# audio_spectrum.net
KiCad netlist of a schematic drawn in EAGLE
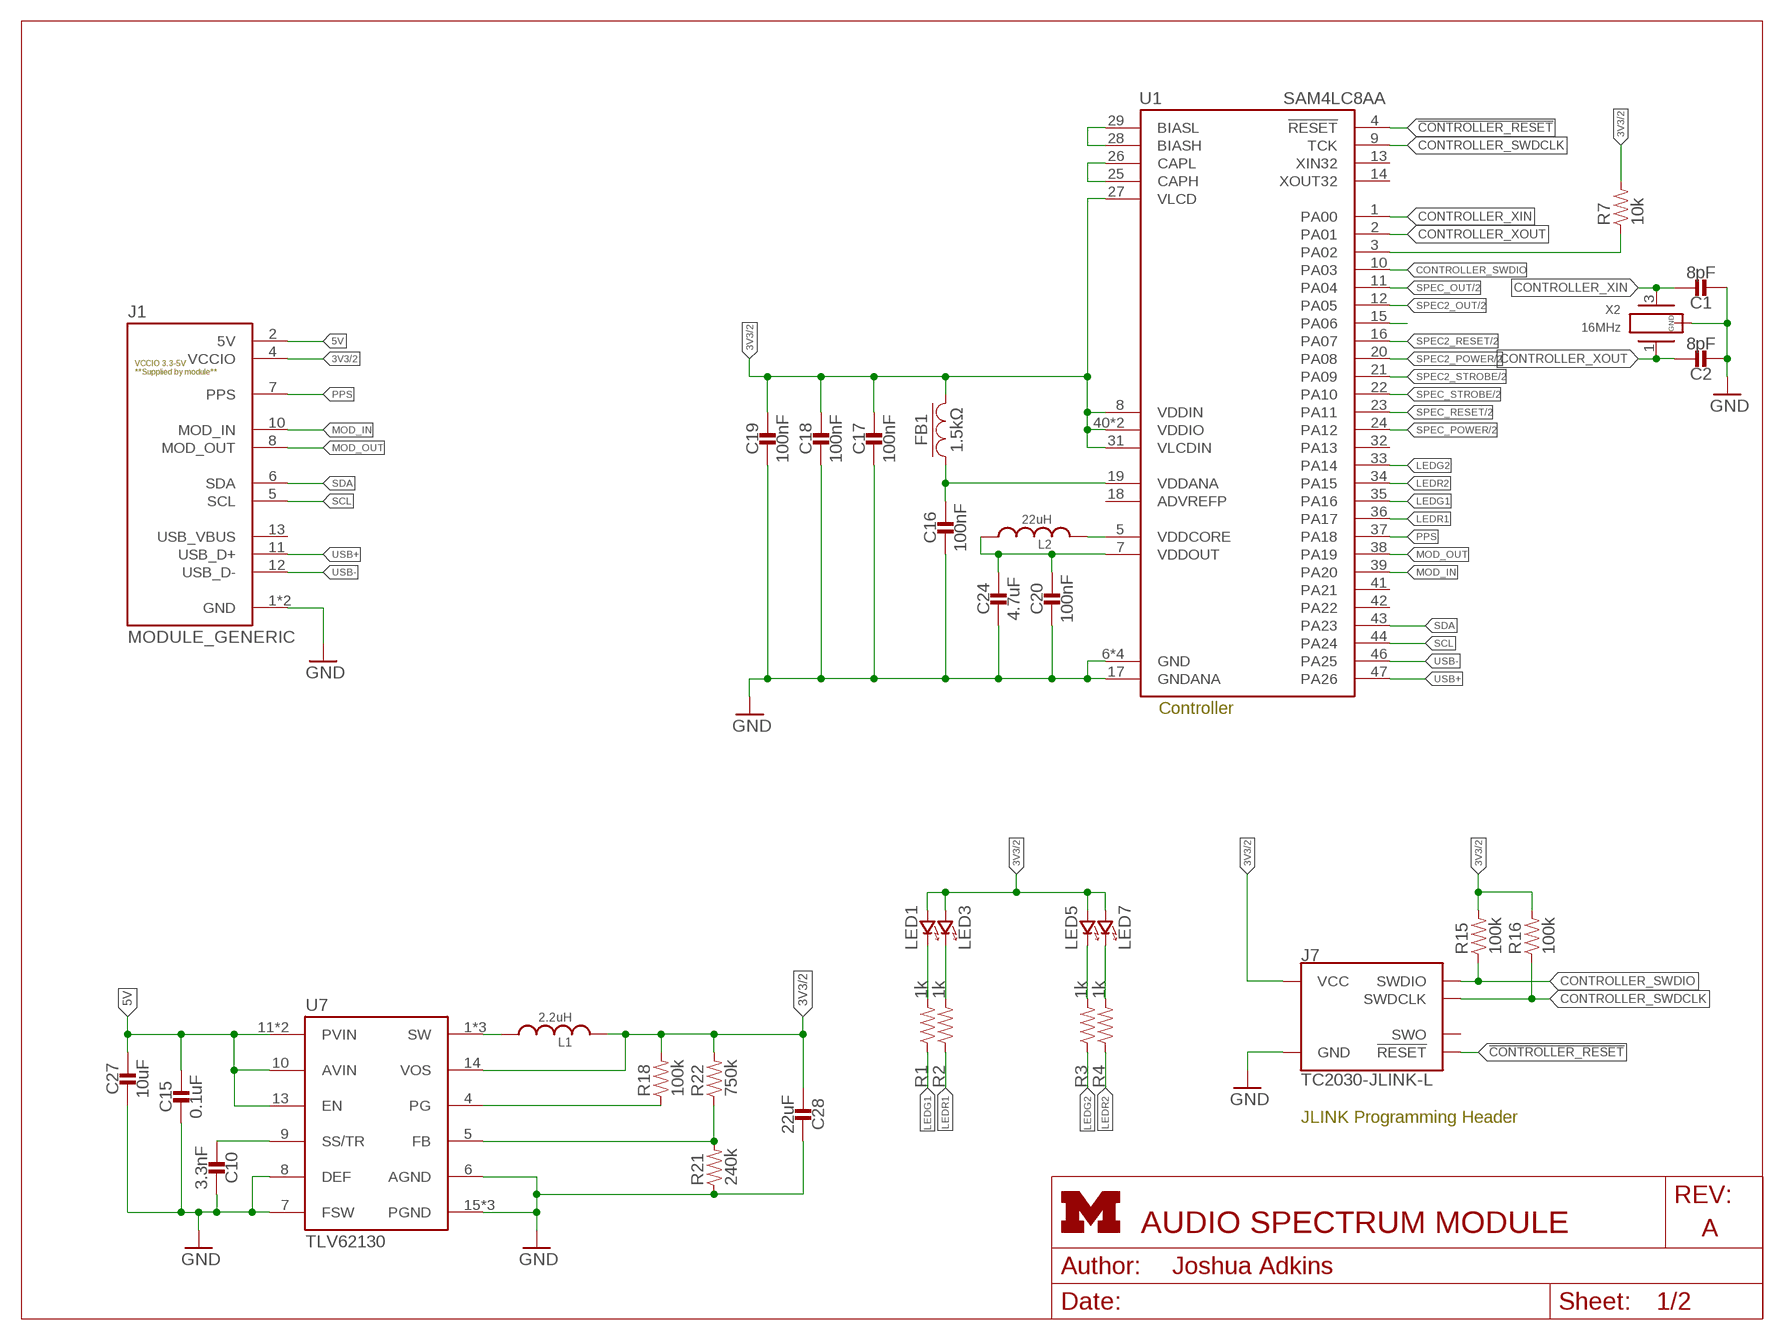
[diagram p0: schematic, sheet 1]
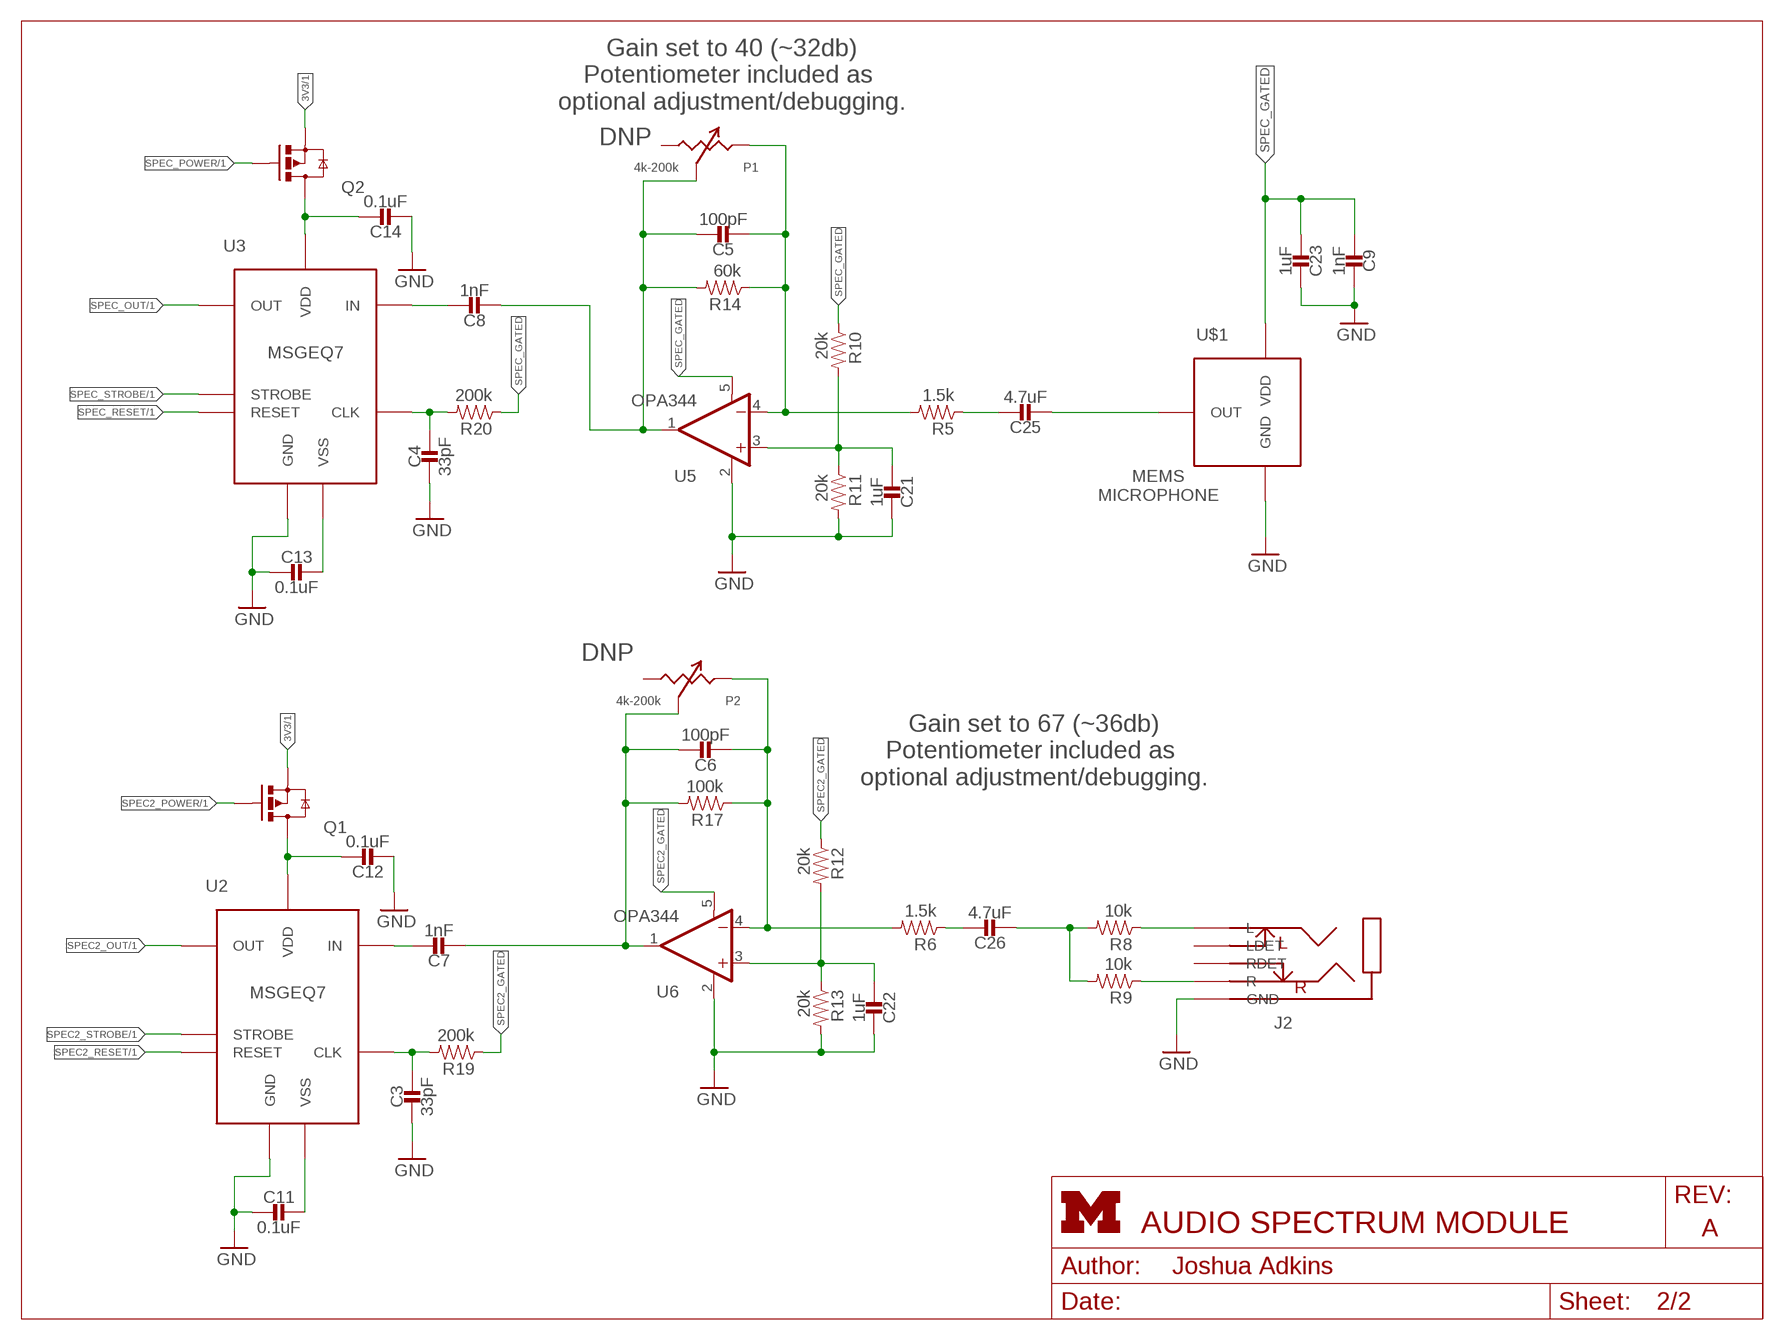
[diagram p1: schematic, sheet 2]

(export (version "E")
  (design (tool "Eeschema 10.0.6"))
  (components
    (comp (ref "C1")
      (value "8pF")
      (footprint "eagle-import:0603_CAP")
      (libsource (lib "eagle-import") (part "CAPACITOR0603_CAP"))
    )
    (comp (ref "C2")
      (value "8pF")
      (footprint "eagle-import:0603_CAP")
      (libsource (lib "eagle-import") (part "CAPACITOR0603_CAP"))
    )
    (comp (ref "C10")
      (value "3.3nF")
      (footprint "eagle-import:0603_CAP")
      (libsource (lib "eagle-import") (part "CAPACITOR0603_CAP"))
    )
    (comp (ref "C15")
      (value "0.1uF")
      (footprint "eagle-import:0603_CAP")
      (libsource (lib "eagle-import") (part "CAPACITOR0603_CAP"))
    )
    (comp (ref "C16")
      (value "100nF")
      (footprint "eagle-import:0603_CAP")
      (libsource (lib "eagle-import") (part "CAPACITOR0603_CAP"))
    )
    (comp (ref "C17")
      (value "100nF")
      (footprint "eagle-import:0603_CAP")
      (libsource (lib "eagle-import") (part "CAPACITOR0603_CAP"))
    )
    (comp (ref "C18")
      (value "100nF")
      (footprint "eagle-import:0603_CAP")
      (libsource (lib "eagle-import") (part "CAPACITOR0603_CAP"))
    )
    (comp (ref "C19")
      (value "100nF")
      (footprint "eagle-import:0603_CAP")
      (libsource (lib "eagle-import") (part "CAPACITOR0603_CAP"))
    )
    (comp (ref "C20")
      (value "100nF")
      (footprint "eagle-import:0603_CAP")
      (libsource (lib "eagle-import") (part "CAPACITOR0603_CAP"))
    )
    (comp (ref "C24")
      (value "4.7uF")
      (footprint "eagle-import:0603_CAP")
      (libsource (lib "eagle-import") (part "CAPACITOR0603_CAP"))
    )
    (comp (ref "C27")
      (value "10uF")
      (footprint "eagle-import:0603_CAP")
      (libsource (lib "eagle-import") (part "CAPACITOR0603_CAP"))
    )
    (comp (ref "C28")
      (value "22uF")
      (footprint "eagle-import:0603_CAP")
      (libsource (lib "eagle-import") (part "CAPACITOR0603_CAP"))
    )
    (comp (ref "FB1")
      (value "1.5kΩ")
      (footprint "eagle-import:0603_CAP")
      (libsource (lib "eagle-import") (part "FERRITE_BEAD0603"))
    )
    (comp (ref "J1")
      (value "MODULE_GENERIC")
      (footprint "eagle-import:MODULE_GENERIC")
      (libsource (lib "eagle-import") (part "MODULE_GENERIC"))
    )
    (comp (ref "J7")
      (value "TC2030-JLINK-L")
      (footprint "eagle-import:TC2030-IDC")
      (libsource (lib "eagle-import") (part "TC2030-JLINK-L"))
    )
    (comp (ref "L1")
      (value "2.2uH")
      (footprint "eagle-import:IHL-1212BZ-11")
      (libsource (lib "eagle-import") (part "INDUCTORIHL"))
    )
    (comp (ref "L2")
      (value "22uH")
      (footprint "eagle-import:1212")
      (libsource (lib "eagle-import") (part "LHQ3NP"))
    )
    (comp (ref "LED1")
      (value "LED0603")
      (footprint "eagle-import:LED-0603")
      (libsource (lib "eagle-import") (part "LED0603"))
    )
    (comp (ref "LED3")
      (value "LED0603")
      (footprint "eagle-import:LED-0603")
      (libsource (lib "eagle-import") (part "LED0603"))
    )
    (comp (ref "LED5")
      (value "LED0603")
      (footprint "eagle-import:LED-0603")
      (libsource (lib "eagle-import") (part "LED0603"))
    )
    (comp (ref "LED7")
      (value "LED0603")
      (footprint "eagle-import:LED-0603")
      (libsource (lib "eagle-import") (part "LED0603"))
    )
    (comp (ref "R1")
      (value "1k")
      (footprint "eagle-import:0603-RES")
      (libsource (lib "eagle-import") (part "RESISTOR0603_RES"))
    )
    (comp (ref "R2")
      (value "1k")
      (footprint "eagle-import:0603-RES")
      (libsource (lib "eagle-import") (part "RESISTOR0603_RES"))
    )
    (comp (ref "R3")
      (value "1k")
      (footprint "eagle-import:0603-RES")
      (libsource (lib "eagle-import") (part "RESISTOR0603_RES"))
    )
    (comp (ref "R4")
      (value "1k")
      (footprint "eagle-import:0603-RES")
      (libsource (lib "eagle-import") (part "RESISTOR0603_RES"))
    )
    (comp (ref "R7")
      (value "10k")
      (footprint "eagle-import:0603-RES")
      (libsource (lib "eagle-import") (part "RESISTOR0603_RES"))
    )
    (comp (ref "R15")
      (value "100k")
      (footprint "eagle-import:0603-RES")
      (libsource (lib "eagle-import") (part "RESISTOR0603_RES"))
    )
    (comp (ref "R16")
      (value "100k")
      (footprint "eagle-import:0603-RES")
      (libsource (lib "eagle-import") (part "RESISTOR0603_RES"))
    )
    (comp (ref "R18")
      (value "100k")
      (footprint "eagle-import:0603-RES")
      (libsource (lib "eagle-import") (part "RESISTOR0603_RES"))
    )
    (comp (ref "R21")
      (value "240k")
      (footprint "eagle-import:0603-RES")
      (libsource (lib "eagle-import") (part "RESISTOR0603_RES"))
    )
    (comp (ref "R22")
      (value "750k")
      (footprint "eagle-import:0603-RES")
      (libsource (lib "eagle-import") (part "RESISTOR0603_RES"))
    )
    (comp (ref "U1")
      (value "SAM4LC8AA")
      (footprint "eagle-import:QFN-48-7MM")
      (libsource (lib "eagle-import") (part "SAM4LC8AA"))
    )
    (comp (ref "U7")
      (value "TLV62130")
      (footprint "eagle-import:TQFN-16_3MM")
      (libsource (lib "eagle-import") (part "TLV62130"))
    )
    (comp (ref "X2")
      (value "16MHz")
      (footprint "eagle-import:FHXXX")
      (libsource (lib "eagle-import") (part "FH1600015"))
    )
    (comp (ref "C3")
      (value "33pF")
      (footprint "eagle-import:0603_CAP")
      (libsource (lib "eagle-import") (part "CAPACITOR0603_CAP"))
    )
    (comp (ref "C4")
      (value "33pF")
      (footprint "eagle-import:0603_CAP")
      (libsource (lib "eagle-import") (part "CAPACITOR0603_CAP"))
    )
    (comp (ref "C5")
      (value "100pF")
      (footprint "eagle-import:0603_CAP")
      (libsource (lib "eagle-import") (part "CAPACITOR0603_CAP"))
    )
    (comp (ref "C6")
      (value "100pF")
      (footprint "eagle-import:0603_CAP")
      (libsource (lib "eagle-import") (part "CAPACITOR0603_CAP"))
    )
    (comp (ref "C7")
      (value "1nF")
      (footprint "eagle-import:0603_CAP")
      (libsource (lib "eagle-import") (part "CAPACITOR0603_CAP"))
    )
    (comp (ref "C8")
      (value "1nF")
      (footprint "eagle-import:0603_CAP")
      (libsource (lib "eagle-import") (part "CAPACITOR0603_CAP"))
    )
    (comp (ref "C9")
      (value "1nF")
      (footprint "eagle-import:0603_CAP")
      (libsource (lib "eagle-import") (part "CAPACITOR0603_CAP"))
    )
    (comp (ref "C11")
      (value "0.1uF")
      (footprint "eagle-import:0603_CAP")
      (libsource (lib "eagle-import") (part "CAPACITOR0603_CAP"))
    )
    (comp (ref "C12")
      (value "0.1uF")
      (footprint "eagle-import:0603_CAP")
      (libsource (lib "eagle-import") (part "CAPACITOR0603_CAP"))
    )
    (comp (ref "C13")
      (value "0.1uF")
      (footprint "eagle-import:0603_CAP")
      (libsource (lib "eagle-import") (part "CAPACITOR0603_CAP"))
    )
    (comp (ref "C14")
      (value "0.1uF")
      (footprint "eagle-import:0603_CAP")
      (libsource (lib "eagle-import") (part "CAPACITOR0603_CAP"))
    )
    (comp (ref "C21")
      (value "1uF")
      (footprint "eagle-import:0603_CAP")
      (libsource (lib "eagle-import") (part "CAPACITOR0603_CAP"))
    )
    (comp (ref "C22")
      (value "1uF")
      (footprint "eagle-import:0603_CAP")
      (libsource (lib "eagle-import") (part "CAPACITOR0603_CAP"))
    )
    (comp (ref "C23")
      (value "1uF")
      (footprint "eagle-import:0603_CAP")
      (libsource (lib "eagle-import") (part "CAPACITOR0603_CAP"))
    )
    (comp (ref "C25")
      (value "4.7uF")
      (footprint "eagle-import:0603_CAP")
      (libsource (lib "eagle-import") (part "CAPACITOR0603_CAP"))
    )
    (comp (ref "C26")
      (value "4.7uF")
      (footprint "eagle-import:0603_CAP")
      (libsource (lib "eagle-import") (part "CAPACITOR0603_CAP"))
    )
    (comp (ref "J2")
      (value "AUDIO-JACK-VERTICAL")
      (footprint "eagle-import:AUDIO-JACK-VERTICAL")
      (libsource (lib "eagle-import") (part "AUDIO-JACK-VERTICAL"))
    )
    (comp (ref "P1")
      (value "4k-200k")
      (footprint "eagle-import:TC33X-2")
      (libsource (lib "eagle-import") (part "POTTC33X"))
    )
    (comp (ref "P2")
      (value "4k-200k")
      (footprint "eagle-import:TC33X-2")
      (libsource (lib "eagle-import") (part "POTTC33X"))
    )
    (comp (ref "Q1")
      (value "NX3008PBK")
      (footprint "eagle-import:SOT23-3")
      (libsource (lib "eagle-import") (part "NX3008PBK"))
    )
    (comp (ref "Q2")
      (value "NX3008PBK")
      (footprint "eagle-import:SOT23-3")
      (libsource (lib "eagle-import") (part "NX3008PBK"))
    )
    (comp (ref "R5")
      (value "1.5k")
      (footprint "eagle-import:0603-RES")
      (libsource (lib "eagle-import") (part "RESISTOR0603_RES"))
    )
    (comp (ref "R6")
      (value "1.5k")
      (footprint "eagle-import:0603-RES")
      (libsource (lib "eagle-import") (part "RESISTOR0603_RES"))
    )
    (comp (ref "R8")
      (value "10k")
      (footprint "eagle-import:0603-RES")
      (libsource (lib "eagle-import") (part "RESISTOR0603_RES"))
    )
    (comp (ref "R9")
      (value "10k")
      (footprint "eagle-import:0603-RES")
      (libsource (lib "eagle-import") (part "RESISTOR0603_RES"))
    )
    (comp (ref "R10")
      (value "20k")
      (footprint "eagle-import:0603-RES")
      (libsource (lib "eagle-import") (part "RESISTOR0603_RES"))
    )
    (comp (ref "R11")
      (value "20k")
      (footprint "eagle-import:0603-RES")
      (libsource (lib "eagle-import") (part "RESISTOR0603_RES"))
    )
    (comp (ref "R12")
      (value "20k")
      (footprint "eagle-import:0603-RES")
      (libsource (lib "eagle-import") (part "RESISTOR0603_RES"))
    )
    (comp (ref "R13")
      (value "20k")
      (footprint "eagle-import:0603-RES")
      (libsource (lib "eagle-import") (part "RESISTOR0603_RES"))
    )
    (comp (ref "R14")
      (value "60k")
      (footprint "eagle-import:0603-RES")
      (libsource (lib "eagle-import") (part "RESISTOR0603_RES"))
    )
    (comp (ref "R17")
      (value "100k")
      (footprint "eagle-import:0603-RES")
      (libsource (lib "eagle-import") (part "RESISTOR0603_RES"))
    )
    (comp (ref "R19")
      (value "200k")
      (footprint "eagle-import:0603-RES")
      (libsource (lib "eagle-import") (part "RESISTOR0603_RES"))
    )
    (comp (ref "R20")
      (value "200k")
      (footprint "eagle-import:0603-RES")
      (libsource (lib "eagle-import") (part "RESISTOR0603_RES"))
    )
    (comp (ref "U$1")
      (value "MP23AB02B")
      (footprint "eagle-import:MP23AB02B")
      (libsource (lib "eagle-import") (part "MP23AB02B"))
    )
    (comp (ref "U2")
      (value "MSGEQ7")
      (footprint "eagle-import:DIP-8")
      (libsource (lib "eagle-import") (part "MSGEQ7"))
    )
    (comp (ref "U3")
      (value "MSGEQ7")
      (footprint "eagle-import:DIP-8")
      (libsource (lib "eagle-import") (part "MSGEQ7"))
    )
    (comp (ref "U5")
      (value "OPA344")
      (footprint "eagle-import:SOT23-5")
      (libsource (lib "eagle-import") (part "OPA344"))
    )
    (comp (ref "U6")
      (value "OPA344")
      (footprint "eagle-import:SOT23-5")
      (libsource (lib "eagle-import") (part "OPA344"))
    )
  )
  (nets
    (net (code "1") (name "3V3") (class "Default")
      (node (ref "C17") (pin "1") (pinfunction "1_1") (pintype "bidirectional"))
      (node (ref "C18") (pin "1") (pinfunction "1_1") (pintype "bidirectional"))
      (node (ref "C19") (pin "1") (pinfunction "1_1") (pintype "bidirectional"))
      (node (ref "C28") (pin "2") (pinfunction "2_2") (pintype "bidirectional"))
      (node (ref "FB1") (pin "2") (pinfunction "P$2_2") (pintype "bidirectional"))
      (node (ref "J1") (pin "4") (pinfunction "VCCIO_4") (pintype "bidirectional"))
      (node (ref "J7") (pin "1") (pinfunction "VCC_1") (pintype "bidirectional"))
      (node (ref "L1") (pin "P$2") (pinfunction "2_P$2") (pintype "bidirectional"))
      (node (ref "LED1") (pin "A") (pinfunction "ANODE_A") (pintype "bidirectional"))
      (node (ref "LED3") (pin "A") (pinfunction "ANODE_A") (pintype "bidirectional"))
      (node (ref "LED5") (pin "A") (pinfunction "ANODE_A") (pintype "bidirectional"))
      (node (ref "LED7") (pin "A") (pinfunction "ANODE_A") (pintype "bidirectional"))
      (node (ref "Q1") (pin "2") (pinfunction "S_2") (pintype "passive"))
      (node (ref "Q2") (pin "2") (pinfunction "S_2") (pintype "passive"))
      (node (ref "R15") (pin "2") (pinfunction "2_2") (pintype "passive"))
      (node (ref "R16") (pin "2") (pinfunction "2_2") (pintype "passive"))
      (node (ref "R18") (pin "2") (pinfunction "2_2") (pintype "passive"))
      (node (ref "R22") (pin "2") (pinfunction "2_2") (pintype "passive"))
      (node (ref "R7") (pin "2") (pinfunction "2_2") (pintype "passive"))
      (node (ref "U1") (pin "27") (pinfunction "VLCD_27") (pintype "bidirectional"))
      (node (ref "U1") (pin "31") (pinfunction "VLCDIN_31") (pintype "power_in"))
      (node (ref "U1") (pin "40") (pinfunction "VDDIO_40") (pintype "power_in"))
      (node (ref "U1") (pin "45") (pinfunction "VDDIO_45") (pintype "power_in"))
      (node (ref "U1") (pin "8") (pinfunction "VDDIN_8") (pintype "power_in"))
      (node (ref "U7") (pin "14") (pinfunction "VOS_14") (pintype "bidirectional"))
    )
    (net (code "2") (name "5V") (class "Default")
      (node (ref "C15") (pin "1") (pinfunction "1_1") (pintype "bidirectional"))
      (node (ref "C27") (pin "1") (pinfunction "1_1") (pintype "bidirectional"))
      (node (ref "J1") (pin "2") (pinfunction "5V_2") (pintype "bidirectional"))
      (node (ref "U7") (pin "10") (pinfunction "AVIN_10") (pintype "bidirectional"))
      (node (ref "U7") (pin "11") (pinfunction "PVIN_11") (pintype "bidirectional"))
      (node (ref "U7") (pin "12") (pinfunction "PVIN_12") (pintype "bidirectional"))
      (node (ref "U7") (pin "13") (pinfunction "EN_13") (pintype "bidirectional"))
    )
    (net (code "3") (name "CONTROLLER_SWDCLK") (class "Default")
      (node (ref "J7") (pin "4") (pinfunction "SWDCLK_4") (pintype "bidirectional"))
      (node (ref "R16") (pin "1") (pinfunction "1_1") (pintype "passive"))
      (node (ref "U1") (pin "9") (pinfunction "TCK_9") (pintype "bidirectional"))
    )
    (net (code "4") (name "CONTROLLER_SWDIO") (class "Default")
      (node (ref "J7") (pin "2") (pinfunction "SWDIO_2") (pintype "bidirectional"))
      (node (ref "R15") (pin "1") (pinfunction "1_1") (pintype "passive"))
      (node (ref "U1") (pin "10") (pinfunction "PA03_10") (pintype "bidirectional"))
    )
    (net (code "5") (name "CONTROLLER_XIN") (class "Default")
      (node (ref "C1") (pin "1") (pinfunction "1_1") (pintype "bidirectional"))
      (node (ref "U1") (pin "1") (pinfunction "PA00_1") (pintype "bidirectional"))
      (node (ref "X2") (pin "3") (pinfunction "2_3") (pintype "bidirectional"))
    )
    (net (code "6") (name "CONTROLLER_XOUT") (class "Default")
      (node (ref "C2") (pin "1") (pinfunction "1_1") (pintype "bidirectional"))
      (node (ref "U1") (pin "2") (pinfunction "PA01_2") (pintype "bidirectional"))
      (node (ref "X2") (pin "1") (pinfunction "1_1") (pintype "bidirectional"))
    )
    (net (code "7") (name "GND") (class "Default")
      (node (ref "C1") (pin "2") (pinfunction "2_2") (pintype "bidirectional"))
      (node (ref "C10") (pin "1") (pinfunction "1_1") (pintype "bidirectional"))
      (node (ref "C11") (pin "2") (pinfunction "2_2") (pintype "bidirectional"))
      (node (ref "C12") (pin "2") (pinfunction "2_2") (pintype "bidirectional"))
      (node (ref "C13") (pin "2") (pinfunction "2_2") (pintype "bidirectional"))
      (node (ref "C14") (pin "2") (pinfunction "2_2") (pintype "bidirectional"))
      (node (ref "C15") (pin "2") (pinfunction "2_2") (pintype "bidirectional"))
      (node (ref "C16") (pin "2") (pinfunction "2_2") (pintype "bidirectional"))
      (node (ref "C17") (pin "2") (pinfunction "2_2") (pintype "bidirectional"))
      (node (ref "C18") (pin "2") (pinfunction "2_2") (pintype "bidirectional"))
      (node (ref "C19") (pin "2") (pinfunction "2_2") (pintype "bidirectional"))
      (node (ref "C2") (pin "2") (pinfunction "2_2") (pintype "bidirectional"))
      (node (ref "C20") (pin "2") (pinfunction "2_2") (pintype "bidirectional"))
      (node (ref "C21") (pin "1") (pinfunction "1_1") (pintype "bidirectional"))
      (node (ref "C22") (pin "1") (pinfunction "1_1") (pintype "bidirectional"))
      (node (ref "C23") (pin "1") (pinfunction "1_1") (pintype "bidirectional"))
      (node (ref "C24") (pin "2") (pinfunction "2_2") (pintype "bidirectional"))
      (node (ref "C27") (pin "2") (pinfunction "2_2") (pintype "bidirectional"))
      (node (ref "C28") (pin "1") (pinfunction "1_1") (pintype "bidirectional"))
      (node (ref "C3") (pin "2") (pinfunction "2_2") (pintype "bidirectional"))
      (node (ref "C4") (pin "2") (pinfunction "2_2") (pintype "bidirectional"))
      (node (ref "C9") (pin "1") (pinfunction "1_1") (pintype "bidirectional"))
      (node (ref "J1") (pin "1") (pinfunction "GND_1") (pintype "bidirectional"))
      (node (ref "J1") (pin "14") (pinfunction "GND_14") (pintype "bidirectional"))
      (node (ref "J2") (pin "5") (pinfunction "GND_5") (pintype "bidirectional"))
      (node (ref "J7") (pin "5") (pinfunction "GND_5") (pintype "bidirectional"))
      (node (ref "R11") (pin "2") (pinfunction "2_2") (pintype "passive"))
      (node (ref "R13") (pin "2") (pinfunction "2_2") (pintype "passive"))
      (node (ref "R21") (pin "1") (pinfunction "1_1") (pintype "passive"))
      (node (ref "U$1") (pin "3") (pinfunction "GND_3") (pintype "bidirectional"))
      (node (ref "U1") (pin "17") (pinfunction "GNDANA_17") (pintype "power_in"))
      (node (ref "U1") (pin "30") (pinfunction "GND_30") (pintype "power_in"))
      (node (ref "U1") (pin "48") (pinfunction "GND_48") (pintype "power_in"))
      (node (ref "U1") (pin "6") (pinfunction "GND_6") (pintype "power_in"))
      (node (ref "U1") (pin "THERMAL") (pinfunction "GND_THERMAL") (pintype "power_in"))
      (node (ref "U2") (pin "6") (pinfunction "GND_6") (pintype "bidirectional"))
      (node (ref "U3") (pin "6") (pinfunction "GND_6") (pintype "bidirectional"))
      (node (ref "U5") (pin "2") (pinfunction "V-_2") (pintype "power_in"))
      (node (ref "U6") (pin "2") (pinfunction "V-_2") (pintype "power_in"))
      (node (ref "U7") (pin "15") (pinfunction "PGND_15") (pintype "bidirectional"))
      (node (ref "U7") (pin "16") (pinfunction "PGND_16") (pintype "bidirectional"))
      (node (ref "U7") (pin "6") (pinfunction "AGND_6") (pintype "bidirectional"))
      (node (ref "U7") (pin "7") (pinfunction "FSW_7") (pintype "bidirectional"))
      (node (ref "U7") (pin "8") (pinfunction "DEF_8") (pintype "bidirectional"))
      (node (ref "U7") (pin "GND") (pinfunction "PGND_GND") (pintype "bidirectional"))
      (node (ref "X2") (pin "2") (pinfunction "GND_2") (pintype "bidirectional"))
      (node (ref "X2") (pin "4") (pinfunction "GND_4") (pintype "bidirectional"))
    )
    (net (code "8") (name "LEDG1") (class "Default")
      (node (ref "R1") (pin "1") (pinfunction "1_1") (pintype "passive"))
      (node (ref "U1") (pin "35") (pinfunction "PA16_35") (pintype "bidirectional"))
    )
    (net (code "9") (name "LEDG2") (class "Default")
      (node (ref "R3") (pin "1") (pinfunction "1_1") (pintype "passive"))
      (node (ref "U1") (pin "33") (pinfunction "PA14_33") (pintype "bidirectional"))
    )
    (net (code "10") (name "LEDR1") (class "Default")
      (node (ref "R2") (pin "1") (pinfunction "1_1") (pintype "passive"))
      (node (ref "U1") (pin "36") (pinfunction "PA17_36") (pintype "bidirectional"))
    )
    (net (code "11") (name "LEDR2") (class "Default")
      (node (ref "R4") (pin "1") (pinfunction "1_1") (pintype "passive"))
      (node (ref "U1") (pin "34") (pinfunction "PA15_34") (pintype "bidirectional"))
    )
    (net (code "12") (name "MOD_IN") (class "Default")
      (node (ref "J1") (pin "10") (pinfunction "MOD_IN_10") (pintype "bidirectional"))
      (node (ref "U1") (pin "39") (pinfunction "PA20_39") (pintype "bidirectional"))
    )
    (net (code "13") (name "MOD_OUT") (class "Default")
      (node (ref "J1") (pin "8") (pinfunction "MOD_OUT_8") (pintype "bidirectional"))
      (node (ref "U1") (pin "38") (pinfunction "PA19_38") (pintype "bidirectional"))
    )
    (net (code "14") (name "Net-(C25-Pad1)") (class "Default")
      (node (ref "C25") (pin "1") (pinfunction "1_1") (pintype "bidirectional"))
      (node (ref "R5") (pin "1") (pinfunction "1_1") (pintype "passive"))
    )
    (net (code "15") (name "Net-(C26-Pad1)") (class "Default")
      (node (ref "C26") (pin "1") (pinfunction "1_1") (pintype "bidirectional"))
      (node (ref "R6") (pin "1") (pinfunction "1_1") (pintype "passive"))
    )
    (net (code "16") (name "Net-(C26-Pad2)") (class "Default")
      (node (ref "C26") (pin "2") (pinfunction "2_2") (pintype "bidirectional"))
      (node (ref "R8") (pin "2") (pinfunction "2_2") (pintype "passive"))
      (node (ref "R9") (pin "2") (pinfunction "2_2") (pintype "passive"))
    )
    (net (code "17") (name "Net-(FB1-P$1)") (class "Default")
      (node (ref "C16") (pin "1") (pinfunction "1_1") (pintype "bidirectional"))
      (node (ref "FB1") (pin "1") (pinfunction "P$1_1") (pintype "bidirectional"))
      (node (ref "U1") (pin "19") (pinfunction "VDDANA_19") (pintype "power_in"))
    )
    (net (code "18") (name "Net-(J2-L)") (class "Default")
      (node (ref "J2") (pin "4") (pinfunction "L_4") (pintype "bidirectional"))
      (node (ref "R8") (pin "1") (pinfunction "1_1") (pintype "passive"))
    )
    (net (code "19") (name "Net-(J2-R)") (class "Default")
      (node (ref "J2") (pin "1") (pinfunction "R_1") (pintype "bidirectional"))
      (node (ref "R9") (pin "1") (pinfunction "1_1") (pintype "passive"))
    )
    (net (code "20") (name "Net-(L1-1)") (class "Default")
      (node (ref "L1") (pin "P$1") (pinfunction "1_P$1") (pintype "bidirectional"))
      (node (ref "U7") (pin "1") (pinfunction "SW_1") (pintype "bidirectional"))
      (node (ref "U7") (pin "2") (pinfunction "SW_2") (pintype "bidirectional"))
      (node (ref "U7") (pin "3") (pinfunction "SW_3") (pintype "bidirectional"))
    )
    (net (code "21") (name "Net-(L2-1)") (class "Default")
      (node (ref "C20") (pin "1") (pinfunction "1_1") (pintype "bidirectional"))
      (node (ref "C24") (pin "1") (pinfunction "1_1") (pintype "bidirectional"))
      (node (ref "L2") (pin "P$1") (pinfunction "1_P$1") (pintype "bidirectional"))
      (node (ref "U1") (pin "7") (pinfunction "VDDOUT_7") (pintype "power_in"))
    )
    (net (code "22") (name "Net-(L2-2)") (class "Default")
      (node (ref "L2") (pin "P$2") (pinfunction "2_P$2") (pintype "bidirectional"))
      (node (ref "U1") (pin "5") (pinfunction "VDDCORE_5") (pintype "power_in"))
    )
    (net (code "23") (name "Net-(LED1-CATHODE)") (class "Default")
      (node (ref "LED1") (pin "C") (pinfunction "CATHODE_C") (pintype "bidirectional"))
      (node (ref "R1") (pin "2") (pinfunction "2_2") (pintype "passive"))
    )
    (net (code "24") (name "Net-(LED3-CATHODE)") (class "Default")
      (node (ref "LED3") (pin "C") (pinfunction "CATHODE_C") (pintype "bidirectional"))
      (node (ref "R2") (pin "2") (pinfunction "2_2") (pintype "passive"))
    )
    (net (code "25") (name "Net-(LED5-CATHODE)") (class "Default")
      (node (ref "LED5") (pin "C") (pinfunction "CATHODE_C") (pintype "bidirectional"))
      (node (ref "R3") (pin "2") (pinfunction "2_2") (pintype "passive"))
    )
    (net (code "26") (name "Net-(LED7-CATHODE)") (class "Default")
      (node (ref "LED7") (pin "C") (pinfunction "CATHODE_C") (pintype "bidirectional"))
      (node (ref "R4") (pin "2") (pinfunction "2_2") (pintype "passive"))
    )
    (net (code "27") (name "Net-(P1-CW)") (class "Default")
      (node (ref "C5") (pin "2") (pinfunction "2_2") (pintype "bidirectional"))
      (node (ref "P1") (pin "2") (pinfunction "CW_2") (pintype "bidirectional"))
      (node (ref "R14") (pin "1") (pinfunction "1_1") (pintype "passive"))
      (node (ref "R5") (pin "2") (pinfunction "2_2") (pintype "passive"))
      (node (ref "U5") (pin "4") (pinfunction "-IN_4") (pintype "input"))
    )
    (net (code "28") (name "Net-(P1-W)") (class "Default")
      (node (ref "C5") (pin "1") (pinfunction "1_1") (pintype "bidirectional"))
      (node (ref "C8") (pin "2") (pinfunction "2_2") (pintype "bidirectional"))
      (node (ref "P1") (pin "3") (pinfunction "W_3") (pintype "bidirectional"))
      (node (ref "R14") (pin "2") (pinfunction "2_2") (pintype "passive"))
      (node (ref "U5") (pin "1") (pinfunction "OUT_1") (pintype "output"))
    )
    (net (code "29") (name "Net-(P2-CW)") (class "Default")
      (node (ref "C6") (pin "2") (pinfunction "2_2") (pintype "bidirectional"))
      (node (ref "P2") (pin "2") (pinfunction "CW_2") (pintype "bidirectional"))
      (node (ref "R17") (pin "1") (pinfunction "1_1") (pintype "passive"))
      (node (ref "R6") (pin "2") (pinfunction "2_2") (pintype "passive"))
      (node (ref "U6") (pin "4") (pinfunction "-IN_4") (pintype "input"))
    )
    (net (code "30") (name "Net-(P2-W)") (class "Default")
      (node (ref "C6") (pin "1") (pinfunction "1_1") (pintype "bidirectional"))
      (node (ref "C7") (pin "2") (pinfunction "2_2") (pintype "bidirectional"))
      (node (ref "P2") (pin "3") (pinfunction "W_3") (pintype "bidirectional"))
      (node (ref "R17") (pin "2") (pinfunction "2_2") (pintype "passive"))
      (node (ref "U6") (pin "1") (pinfunction "OUT_1") (pintype "output"))
    )
    (net (code "31") (name "Net-(U$1-OUT)") (class "Default")
      (node (ref "C25") (pin "2") (pinfunction "2_2") (pintype "bidirectional"))
      (node (ref "U$1") (pin "1") (pinfunction "OUT_1") (pintype "bidirectional"))
    )
    (net (code "32") (name "Net-(U1-BIASH)") (class "Default")
      (node (ref "U1") (pin "28") (pinfunction "BIASH_28") (pintype "bidirectional"))
      (node (ref "U1") (pin "29") (pinfunction "BIASL_29") (pintype "bidirectional"))
    )
    (net (code "33") (name "Net-(U1-CAPH)") (class "Default")
      (node (ref "U1") (pin "25") (pinfunction "CAPH_25") (pintype "bidirectional"))
      (node (ref "U1") (pin "26") (pinfunction "CAPL_26") (pintype "bidirectional"))
    )
    (net (code "34") (name "Net-(U1-PA02)") (class "Default")
      (node (ref "R7") (pin "1") (pinfunction "1_1") (pintype "passive"))
      (node (ref "U1") (pin "3") (pinfunction "PA02_3") (pintype "bidirectional"))
    )
    (net (code "35") (name "Net-(U2-CLK)") (class "Default")
      (node (ref "C3") (pin "1") (pinfunction "1_1") (pintype "bidirectional"))
      (node (ref "R19") (pin "2") (pinfunction "2_2") (pintype "passive"))
      (node (ref "U2") (pin "8") (pinfunction "CLK_8") (pintype "bidirectional"))
    )
    (net (code "36") (name "Net-(U2-IN)") (class "Default")
      (node (ref "C7") (pin "1") (pinfunction "1_1") (pintype "bidirectional"))
      (node (ref "U2") (pin "5") (pinfunction "IN_5") (pintype "bidirectional"))
    )
    (net (code "37") (name "Net-(U2-VSS)") (class "Default")
      (node (ref "C11") (pin "1") (pinfunction "1_1") (pintype "bidirectional"))
      (node (ref "U2") (pin "2") (pinfunction "VSS_2") (pintype "bidirectional"))
    )
    (net (code "38") (name "Net-(U3-CLK)") (class "Default")
      (node (ref "C4") (pin "1") (pinfunction "1_1") (pintype "bidirectional"))
      (node (ref "R20") (pin "2") (pinfunction "2_2") (pintype "passive"))
      (node (ref "U3") (pin "8") (pinfunction "CLK_8") (pintype "bidirectional"))
    )
    (net (code "39") (name "Net-(U3-IN)") (class "Default")
      (node (ref "C8") (pin "1") (pinfunction "1_1") (pintype "bidirectional"))
      (node (ref "U3") (pin "5") (pinfunction "IN_5") (pintype "bidirectional"))
    )
    (net (code "40") (name "Net-(U3-VSS)") (class "Default")
      (node (ref "C13") (pin "1") (pinfunction "1_1") (pintype "bidirectional"))
      (node (ref "U3") (pin "2") (pinfunction "VSS_2") (pintype "bidirectional"))
    )
    (net (code "41") (name "Net-(U5-+IN)") (class "Default")
      (node (ref "C21") (pin "2") (pinfunction "2_2") (pintype "bidirectional"))
      (node (ref "R10") (pin "2") (pinfunction "2_2") (pintype "passive"))
      (node (ref "R11") (pin "1") (pinfunction "1_1") (pintype "passive"))
      (node (ref "U5") (pin "3") (pinfunction "+IN_3") (pintype "input"))
    )
    (net (code "42") (name "Net-(U6-+IN)") (class "Default")
      (node (ref "C22") (pin "2") (pinfunction "2_2") (pintype "bidirectional"))
      (node (ref "R12") (pin "2") (pinfunction "2_2") (pintype "passive"))
      (node (ref "R13") (pin "1") (pinfunction "1_1") (pintype "passive"))
      (node (ref "U6") (pin "3") (pinfunction "+IN_3") (pintype "input"))
    )
    (net (code "43") (name "Net-(U7-FB)") (class "Default")
      (node (ref "R21") (pin "2") (pinfunction "2_2") (pintype "passive"))
      (node (ref "R22") (pin "1") (pinfunction "1_1") (pintype "passive"))
      (node (ref "U7") (pin "5") (pinfunction "FB_5") (pintype "bidirectional"))
    )
    (net (code "44") (name "Net-(U7-PG)") (class "Default")
      (node (ref "R18") (pin "1") (pinfunction "1_1") (pintype "passive"))
      (node (ref "U7") (pin "4") (pinfunction "PG_4") (pintype "bidirectional"))
    )
    (net (code "45") (name "Net-(U7-SS{slash}TR)") (class "Default")
      (node (ref "C10") (pin "2") (pinfunction "2_2") (pintype "bidirectional"))
      (node (ref "U7") (pin "9") (pinfunction "SS/TR_9") (pintype "bidirectional"))
    )
    (net (code "46") (name "PPS") (class "Default")
      (node (ref "J1") (pin "7") (pinfunction "PPS_7") (pintype "bidirectional"))
      (node (ref "U1") (pin "37") (pinfunction "PA18_37") (pintype "bidirectional"))
    )
    (net (code "47") (name "SCL") (class "Default")
      (node (ref "J1") (pin "5") (pinfunction "SCL_5") (pintype "bidirectional"))
      (node (ref "U1") (pin "44") (pinfunction "PA24_44") (pintype "bidirectional"))
    )
    (net (code "48") (name "SDA") (class "Default")
      (node (ref "J1") (pin "6") (pinfunction "SDA_6") (pintype "bidirectional"))
      (node (ref "U1") (pin "43") (pinfunction "PA23_43") (pintype "bidirectional"))
    )
    (net (code "49") (name "SPEC2_GATED") (class "Default")
      (node (ref "C12") (pin "1") (pinfunction "1_1") (pintype "bidirectional"))
      (node (ref "Q1") (pin "3") (pinfunction "D_3") (pintype "passive"))
      (node (ref "R12") (pin "1") (pinfunction "1_1") (pintype "passive"))
      (node (ref "R19") (pin "1") (pinfunction "1_1") (pintype "passive"))
      (node (ref "U2") (pin "1") (pinfunction "VDD_1") (pintype "bidirectional"))
      (node (ref "U6") (pin "5") (pinfunction "V+_5") (pintype "power_in"))
    )
    (net (code "50") (name "SPEC2_OUT") (class "Default")
      (node (ref "U1") (pin "12") (pinfunction "PA05_12") (pintype "bidirectional"))
      (node (ref "U2") (pin "3") (pinfunction "OUT_3") (pintype "bidirectional"))
    )
    (net (code "51") (name "SPEC2_POWER") (class "Default")
      (node (ref "Q1") (pin "1") (pinfunction "G_1") (pintype "passive"))
      (node (ref "U1") (pin "20") (pinfunction "PA08_20") (pintype "bidirectional"))
    )
    (net (code "52") (name "SPEC2_RESET") (class "Default")
      (node (ref "U1") (pin "16") (pinfunction "PA07_16") (pintype "bidirectional"))
      (node (ref "U2") (pin "7") (pinfunction "RESET_7") (pintype "bidirectional"))
    )
    (net (code "53") (name "SPEC2_STROBE") (class "Default")
      (node (ref "U1") (pin "21") (pinfunction "PA09_21") (pintype "bidirectional"))
      (node (ref "U2") (pin "4") (pinfunction "STROBE_4") (pintype "bidirectional"))
    )
    (net (code "54") (name "SPEC_GATED") (class "Default")
      (node (ref "C14") (pin "1") (pinfunction "1_1") (pintype "bidirectional"))
      (node (ref "C23") (pin "2") (pinfunction "2_2") (pintype "bidirectional"))
      (node (ref "C9") (pin "2") (pinfunction "2_2") (pintype "bidirectional"))
      (node (ref "Q2") (pin "3") (pinfunction "D_3") (pintype "passive"))
      (node (ref "R10") (pin "1") (pinfunction "1_1") (pintype "passive"))
      (node (ref "R20") (pin "1") (pinfunction "1_1") (pintype "passive"))
      (node (ref "U$1") (pin "2") (pinfunction "VDD_2") (pintype "bidirectional"))
      (node (ref "U3") (pin "1") (pinfunction "VDD_1") (pintype "bidirectional"))
      (node (ref "U5") (pin "5") (pinfunction "V+_5") (pintype "power_in"))
    )
    (net (code "55") (name "SPEC_OUT") (class "Default")
      (node (ref "U1") (pin "11") (pinfunction "PA04_11") (pintype "bidirectional"))
      (node (ref "U3") (pin "3") (pinfunction "OUT_3") (pintype "bidirectional"))
    )
    (net (code "56") (name "SPEC_POWER") (class "Default")
      (node (ref "Q2") (pin "1") (pinfunction "G_1") (pintype "passive"))
      (node (ref "U1") (pin "24") (pinfunction "PA12_24") (pintype "bidirectional"))
    )
    (net (code "57") (name "SPEC_RESET") (class "Default")
      (node (ref "U1") (pin "23") (pinfunction "PA11_23") (pintype "bidirectional"))
      (node (ref "U3") (pin "7") (pinfunction "RESET_7") (pintype "bidirectional"))
    )
    (net (code "58") (name "SPEC_STROBE") (class "Default")
      (node (ref "U1") (pin "22") (pinfunction "PA10_22") (pintype "bidirectional"))
      (node (ref "U3") (pin "4") (pinfunction "STROBE_4") (pintype "bidirectional"))
    )
    (net (code "59") (name "USB+") (class "Default")
      (node (ref "J1") (pin "11") (pinfunction "USB_D+_11") (pintype "bidirectional"))
      (node (ref "U1") (pin "47") (pinfunction "PA26_47") (pintype "bidirectional"))
    )
    (net (code "60") (name "USB-") (class "Default")
      (node (ref "J1") (pin "12") (pinfunction "USB_D-_12") (pintype "bidirectional"))
      (node (ref "U1") (pin "46") (pinfunction "PA25_46") (pintype "bidirectional"))
    )
    (net (code "61") (name "unconnected-(J1-USB_VBUS-Pad13)") (class "Default")
      (node (ref "J1") (pin "13") (pinfunction "USB_VBUS_13") (pintype "bidirectional"))
    )
    (net (code "62") (name "unconnected-(J2-LDET-Pad3)") (class "Default")
      (node (ref "J2") (pin "3") (pinfunction "LDET_3") (pintype "bidirectional"))
    )
    (net (code "63") (name "unconnected-(J2-RDET-Pad2)") (class "Default")
      (node (ref "J2") (pin "2") (pinfunction "RDET_2") (pintype "bidirectional"))
    )
    (net (code "64") (name "unconnected-(J7-SWO-Pad6)") (class "Default")
      (node (ref "J7") (pin "6") (pinfunction "SWO_6") (pintype "bidirectional"))
    )
    (net (code "65") (name "unconnected-(P1-CCW-Pad1)") (class "Default")
      (node (ref "P1") (pin "1") (pinfunction "CCW_1") (pintype "bidirectional"))
    )
    (net (code "66") (name "unconnected-(P2-CCW-Pad1)") (class "Default")
      (node (ref "P2") (pin "1") (pinfunction "CCW_1") (pintype "bidirectional"))
    )
    (net (code "67") (name "unconnected-(U1-ADVREFP-Pad18)") (class "Default")
      (node (ref "U1") (pin "18") (pinfunction "ADVREFP_18") (pintype "bidirectional"))
    )
    (net (code "68") (name "unconnected-(U1-PA06-Pad15)") (class "Default")
      (node (ref "U1") (pin "15") (pinfunction "PA06_15") (pintype "bidirectional"))
    )
    (net (code "69") (name "unconnected-(U1-PA13-Pad32)") (class "Default")
      (node (ref "U1") (pin "32") (pinfunction "PA13_32") (pintype "bidirectional"))
    )
    (net (code "70") (name "unconnected-(U1-PA21-Pad41)") (class "Default")
      (node (ref "U1") (pin "41") (pinfunction "PA21_41") (pintype "bidirectional"))
    )
    (net (code "71") (name "unconnected-(U1-PA22-Pad42)") (class "Default")
      (node (ref "U1") (pin "42") (pinfunction "PA22_42") (pintype "bidirectional"))
    )
    (net (code "72") (name "unconnected-(U1-XIN32-Pad13)") (class "Default")
      (node (ref "U1") (pin "13") (pinfunction "XIN32_13") (pintype "bidirectional"))
    )
    (net (code "73") (name "unconnected-(U1-XOUT32-Pad14)") (class "Default")
      (node (ref "U1") (pin "14") (pinfunction "XOUT32_14") (pintype "bidirectional"))
    )
    (net (code "74") (name "~{CONTROLLER_RESET}") (class "Default")
      (node (ref "J7") (pin "3") (pinfunction "~{RESET}_3") (pintype "bidirectional"))
      (node (ref "U1") (pin "4") (pinfunction "~{RESET}_4") (pintype "bidirectional"))
    )
  )
)
